# LED_CUBE_595.net
KiCad netlist of a schematic drawn in EAGLE
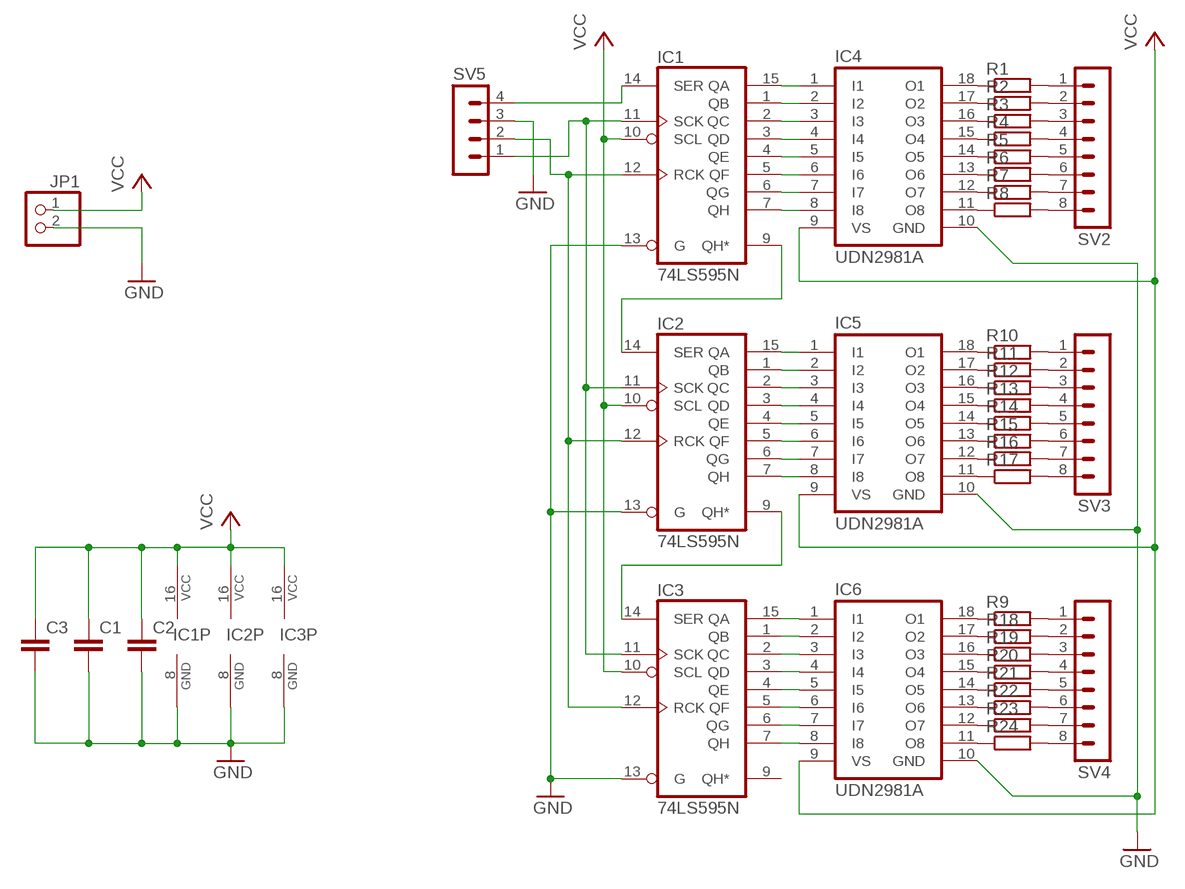
[diagram p0: schematic, sheet 1]

(export (version "E")
  (design (tool "Eeschema 10.0.6"))
  (components
    (comp (ref "C1")
      (value "C-EU025-025X050")
      (footprint "eagle-import:C025-025X050")
      (libsource (lib "eagle-import") (part "C-EU025-025X050"))
    )
    (comp (ref "C2")
      (value "C-EU025-025X050")
      (footprint "eagle-import:C025-025X050")
      (libsource (lib "eagle-import") (part "C-EU025-025X050"))
    )
    (comp (ref "C3")
      (value "C-EU025-025X050")
      (footprint "eagle-import:C025-025X050")
      (libsource (lib "eagle-import") (part "C-EU025-025X050"))
    )
    (comp (ref "IC1")
      (value "74LS595N")
      (footprint "eagle-import:DIL16")
      (libsource (lib "eagle-import") (part "74595NLS"))
    )
    (comp (ref "IC2")
      (value "74LS595N")
      (footprint "eagle-import:DIL16")
      (libsource (lib "eagle-import") (part "74595NLS"))
    )
    (comp (ref "IC3")
      (value "74LS595N")
      (footprint "eagle-import:DIL16")
      (libsource (lib "eagle-import") (part "74595NLS"))
    )
    (comp (ref "IC4")
      (value "UDN2981A")
      (footprint "eagle-import:DIL18")
      (libsource (lib "eagle-import") (part "UDN298A1"))
    )
    (comp (ref "IC5")
      (value "UDN2981A")
      (footprint "eagle-import:DIL18")
      (libsource (lib "eagle-import") (part "UDN298A1"))
    )
    (comp (ref "IC6")
      (value "UDN2981A")
      (footprint "eagle-import:DIL18")
      (libsource (lib "eagle-import") (part "UDN298A1"))
    )
    (comp (ref "JP1")
      (value "PINHD-1X2")
      (footprint "eagle-import:1X02")
      (libsource (lib "eagle-import") (part "PINHD-1X2"))
    )
    (comp (ref "R1")
      (value "R-EU_0204/2V")
      (footprint "eagle-import:0204V")
      (libsource (lib "eagle-import") (part "R-EU_0204/2V"))
    )
    (comp (ref "R2")
      (value "R-EU_0204/2V")
      (footprint "eagle-import:0204V")
      (libsource (lib "eagle-import") (part "R-EU_0204/2V"))
    )
    (comp (ref "R3")
      (value "R-EU_0204/2V")
      (footprint "eagle-import:0204V")
      (libsource (lib "eagle-import") (part "R-EU_0204/2V"))
    )
    (comp (ref "R4")
      (value "R-EU_0204/2V")
      (footprint "eagle-import:0204V")
      (libsource (lib "eagle-import") (part "R-EU_0204/2V"))
    )
    (comp (ref "R5")
      (value "R-EU_0204/2V")
      (footprint "eagle-import:0204V")
      (libsource (lib "eagle-import") (part "R-EU_0204/2V"))
    )
    (comp (ref "R6")
      (value "R-EU_0204/2V")
      (footprint "eagle-import:0204V")
      (libsource (lib "eagle-import") (part "R-EU_0204/2V"))
    )
    (comp (ref "R7")
      (value "R-EU_0204/2V")
      (footprint "eagle-import:0204V")
      (libsource (lib "eagle-import") (part "R-EU_0204/2V"))
    )
    (comp (ref "R8")
      (value "R-EU_0204/2V")
      (footprint "eagle-import:0204V")
      (libsource (lib "eagle-import") (part "R-EU_0204/2V"))
    )
    (comp (ref "R9")
      (value "R-EU_0204/2V")
      (footprint "eagle-import:0204V")
      (libsource (lib "eagle-import") (part "R-EU_0204/2V"))
    )
    (comp (ref "R10")
      (value "R-EU_0204/2V")
      (footprint "eagle-import:0204V")
      (libsource (lib "eagle-import") (part "R-EU_0204/2V"))
    )
    (comp (ref "R11")
      (value "R-EU_0204/2V")
      (footprint "eagle-import:0204V")
      (libsource (lib "eagle-import") (part "R-EU_0204/2V"))
    )
    (comp (ref "R12")
      (value "R-EU_0204/2V")
      (footprint "eagle-import:0204V")
      (libsource (lib "eagle-import") (part "R-EU_0204/2V"))
    )
    (comp (ref "R13")
      (value "R-EU_0204/2V")
      (footprint "eagle-import:0204V")
      (libsource (lib "eagle-import") (part "R-EU_0204/2V"))
    )
    (comp (ref "R14")
      (value "R-EU_0204/2V")
      (footprint "eagle-import:0204V")
      (libsource (lib "eagle-import") (part "R-EU_0204/2V"))
    )
    (comp (ref "R15")
      (value "R-EU_0204/2V")
      (footprint "eagle-import:0204V")
      (libsource (lib "eagle-import") (part "R-EU_0204/2V"))
    )
    (comp (ref "R16")
      (value "R-EU_0204/2V")
      (footprint "eagle-import:0204V")
      (libsource (lib "eagle-import") (part "R-EU_0204/2V"))
    )
    (comp (ref "R17")
      (value "R-EU_0204/2V")
      (footprint "eagle-import:0204V")
      (libsource (lib "eagle-import") (part "R-EU_0204/2V"))
    )
    (comp (ref "R18")
      (value "R-EU_0204/2V")
      (footprint "eagle-import:0204V")
      (libsource (lib "eagle-import") (part "R-EU_0204/2V"))
    )
    (comp (ref "R19")
      (value "R-EU_0204/2V")
      (footprint "eagle-import:0204V")
      (libsource (lib "eagle-import") (part "R-EU_0204/2V"))
    )
    (comp (ref "R20")
      (value "R-EU_0204/2V")
      (footprint "eagle-import:0204V")
      (libsource (lib "eagle-import") (part "R-EU_0204/2V"))
    )
    (comp (ref "R21")
      (value "R-EU_0204/2V")
      (footprint "eagle-import:0204V")
      (libsource (lib "eagle-import") (part "R-EU_0204/2V"))
    )
    (comp (ref "R22")
      (value "R-EU_0204/2V")
      (footprint "eagle-import:0204V")
      (libsource (lib "eagle-import") (part "R-EU_0204/2V"))
    )
    (comp (ref "R23")
      (value "R-EU_0204/2V")
      (footprint "eagle-import:0204V")
      (libsource (lib "eagle-import") (part "R-EU_0204/2V"))
    )
    (comp (ref "R24")
      (value "R-EU_0204/2V")
      (footprint "eagle-import:0204V")
      (libsource (lib "eagle-import") (part "R-EU_0204/2V"))
    )
    (comp (ref "SV2")
      (value "MA08-1")
      (footprint "eagle-import:MA08-1")
      (libsource (lib "eagle-import") (part "MA08-1"))
    )
    (comp (ref "SV3")
      (value "MA08-1")
      (footprint "eagle-import:MA08-1")
      (libsource (lib "eagle-import") (part "MA08-1"))
    )
    (comp (ref "SV4")
      (value "MA08-1")
      (footprint "eagle-import:MA08-1")
      (libsource (lib "eagle-import") (part "MA08-1"))
    )
    (comp (ref "SV5")
      (value "MA04-1")
      (footprint "eagle-import:MA04-1")
      (libsource (lib "eagle-import") (part "MA04-1"))
    )
  )
  (nets
    (net (code "1") (name "GND") (class "Default")
      (node (ref "C1") (pin "2") (pinfunction "2_2") (pintype "passive"))
      (node (ref "C2") (pin "2") (pinfunction "2_2") (pintype "passive"))
      (node (ref "C3") (pin "2") (pinfunction "2_2") (pintype "passive"))
      (node (ref "IC1") (pin "13") (pinfunction "G_13") (pintype "input"))
      (node (ref "IC1") (pin "8") (pinfunction "GND_8") (pintype "power_in"))
      (node (ref "IC2") (pin "13") (pinfunction "G_13") (pintype "input"))
      (node (ref "IC2") (pin "8") (pinfunction "GND_8") (pintype "power_in"))
      (node (ref "IC3") (pin "13") (pinfunction "G_13") (pintype "input"))
      (node (ref "IC3") (pin "8") (pinfunction "GND_8") (pintype "power_in"))
      (node (ref "IC4") (pin "10") (pinfunction "GND_10") (pintype "power_in"))
      (node (ref "IC5") (pin "10") (pinfunction "GND_10") (pintype "power_in"))
      (node (ref "IC6") (pin "10") (pinfunction "GND_10") (pintype "power_in"))
      (node (ref "JP1") (pin "2") (pinfunction "2_2") (pintype "passive"))
      (node (ref "SV5") (pin "3") (pinfunction "3_3") (pintype "passive"))
    )
    (net (code "2") (name "Net-(IC1A-QA)") (class "Default")
      (node (ref "IC1") (pin "15") (pinfunction "QA_15") (pintype "tri_state"))
      (node (ref "IC4") (pin "1") (pinfunction "I1_1") (pintype "input"))
    )
    (net (code "3") (name "Net-(IC1A-QB)") (class "Default")
      (node (ref "IC1") (pin "1") (pinfunction "QB_1") (pintype "tri_state"))
      (node (ref "IC4") (pin "2") (pinfunction "I2_2") (pintype "input"))
    )
    (net (code "4") (name "Net-(IC1A-QC)") (class "Default")
      (node (ref "IC1") (pin "2") (pinfunction "QC_2") (pintype "tri_state"))
      (node (ref "IC4") (pin "3") (pinfunction "I3_3") (pintype "input"))
    )
    (net (code "5") (name "Net-(IC1A-QD)") (class "Default")
      (node (ref "IC1") (pin "3") (pinfunction "QD_3") (pintype "tri_state"))
      (node (ref "IC4") (pin "4") (pinfunction "I4_4") (pintype "input"))
    )
    (net (code "6") (name "Net-(IC1A-QE)") (class "Default")
      (node (ref "IC1") (pin "4") (pinfunction "QE_4") (pintype "tri_state"))
      (node (ref "IC4") (pin "5") (pinfunction "I5_5") (pintype "input"))
    )
    (net (code "7") (name "Net-(IC1A-QF)") (class "Default")
      (node (ref "IC1") (pin "5") (pinfunction "QF_5") (pintype "tri_state"))
      (node (ref "IC4") (pin "6") (pinfunction "I6_6") (pintype "input"))
    )
    (net (code "8") (name "Net-(IC1A-QG)") (class "Default")
      (node (ref "IC1") (pin "6") (pinfunction "QG_6") (pintype "tri_state"))
      (node (ref "IC4") (pin "7") (pinfunction "I7_7") (pintype "input"))
    )
    (net (code "9") (name "Net-(IC1A-QH)") (class "Default")
      (node (ref "IC1") (pin "7") (pinfunction "QH_7") (pintype "tri_state"))
      (node (ref "IC4") (pin "8") (pinfunction "I8_8") (pintype "input"))
    )
    (net (code "10") (name "Net-(IC1A-QH*)") (class "Default")
      (node (ref "IC1") (pin "9") (pinfunction "QH*_9") (pintype "tri_state"))
      (node (ref "IC2") (pin "14") (pinfunction "SER_14") (pintype "input"))
    )
    (net (code "11") (name "Net-(IC1A-RCK)") (class "Default")
      (node (ref "IC1") (pin "12") (pinfunction "RCK_12") (pintype "input"))
      (node (ref "IC2") (pin "12") (pinfunction "RCK_12") (pintype "input"))
      (node (ref "IC3") (pin "12") (pinfunction "RCK_12") (pintype "input"))
      (node (ref "SV5") (pin "2") (pinfunction "2_2") (pintype "passive"))
    )
    (net (code "12") (name "Net-(IC1A-SCK)") (class "Default")
      (node (ref "IC1") (pin "11") (pinfunction "SCK_11") (pintype "input"))
      (node (ref "IC2") (pin "11") (pinfunction "SCK_11") (pintype "input"))
      (node (ref "IC3") (pin "11") (pinfunction "SCK_11") (pintype "input"))
      (node (ref "SV5") (pin "1") (pinfunction "1_1") (pintype "passive"))
    )
    (net (code "13") (name "Net-(IC1A-SER)") (class "Default")
      (node (ref "IC1") (pin "14") (pinfunction "SER_14") (pintype "input"))
      (node (ref "SV5") (pin "4") (pinfunction "4_4") (pintype "passive"))
    )
    (net (code "14") (name "Net-(IC2A-QA)") (class "Default")
      (node (ref "IC2") (pin "15") (pinfunction "QA_15") (pintype "tri_state"))
      (node (ref "IC5") (pin "1") (pinfunction "I1_1") (pintype "input"))
    )
    (net (code "15") (name "Net-(IC2A-QB)") (class "Default")
      (node (ref "IC2") (pin "1") (pinfunction "QB_1") (pintype "tri_state"))
      (node (ref "IC5") (pin "2") (pinfunction "I2_2") (pintype "input"))
    )
    (net (code "16") (name "Net-(IC2A-QC)") (class "Default")
      (node (ref "IC2") (pin "2") (pinfunction "QC_2") (pintype "tri_state"))
      (node (ref "IC5") (pin "3") (pinfunction "I3_3") (pintype "input"))
    )
    (net (code "17") (name "Net-(IC2A-QD)") (class "Default")
      (node (ref "IC2") (pin "3") (pinfunction "QD_3") (pintype "tri_state"))
      (node (ref "IC5") (pin "4") (pinfunction "I4_4") (pintype "input"))
    )
    (net (code "18") (name "Net-(IC2A-QE)") (class "Default")
      (node (ref "IC2") (pin "4") (pinfunction "QE_4") (pintype "tri_state"))
      (node (ref "IC5") (pin "5") (pinfunction "I5_5") (pintype "input"))
    )
    (net (code "19") (name "Net-(IC2A-QF)") (class "Default")
      (node (ref "IC2") (pin "5") (pinfunction "QF_5") (pintype "tri_state"))
      (node (ref "IC5") (pin "6") (pinfunction "I6_6") (pintype "input"))
    )
    (net (code "20") (name "Net-(IC2A-QG)") (class "Default")
      (node (ref "IC2") (pin "6") (pinfunction "QG_6") (pintype "tri_state"))
      (node (ref "IC5") (pin "7") (pinfunction "I7_7") (pintype "input"))
    )
    (net (code "21") (name "Net-(IC2A-QH)") (class "Default")
      (node (ref "IC2") (pin "7") (pinfunction "QH_7") (pintype "tri_state"))
      (node (ref "IC5") (pin "8") (pinfunction "I8_8") (pintype "input"))
    )
    (net (code "22") (name "Net-(IC2A-QH*)") (class "Default")
      (node (ref "IC2") (pin "9") (pinfunction "QH*_9") (pintype "tri_state"))
      (node (ref "IC3") (pin "14") (pinfunction "SER_14") (pintype "input"))
    )
    (net (code "23") (name "Net-(IC3A-QA)") (class "Default")
      (node (ref "IC3") (pin "15") (pinfunction "QA_15") (pintype "tri_state"))
      (node (ref "IC6") (pin "1") (pinfunction "I1_1") (pintype "input"))
    )
    (net (code "24") (name "Net-(IC3A-QB)") (class "Default")
      (node (ref "IC3") (pin "1") (pinfunction "QB_1") (pintype "tri_state"))
      (node (ref "IC6") (pin "2") (pinfunction "I2_2") (pintype "input"))
    )
    (net (code "25") (name "Net-(IC3A-QC)") (class "Default")
      (node (ref "IC3") (pin "2") (pinfunction "QC_2") (pintype "tri_state"))
      (node (ref "IC6") (pin "3") (pinfunction "I3_3") (pintype "input"))
    )
    (net (code "26") (name "Net-(IC3A-QD)") (class "Default")
      (node (ref "IC3") (pin "3") (pinfunction "QD_3") (pintype "tri_state"))
      (node (ref "IC6") (pin "4") (pinfunction "I4_4") (pintype "input"))
    )
    (net (code "27") (name "Net-(IC3A-QE)") (class "Default")
      (node (ref "IC3") (pin "4") (pinfunction "QE_4") (pintype "tri_state"))
      (node (ref "IC6") (pin "5") (pinfunction "I5_5") (pintype "input"))
    )
    (net (code "28") (name "Net-(IC3A-QF)") (class "Default")
      (node (ref "IC3") (pin "5") (pinfunction "QF_5") (pintype "tri_state"))
      (node (ref "IC6") (pin "6") (pinfunction "I6_6") (pintype "input"))
    )
    (net (code "29") (name "Net-(IC3A-QG)") (class "Default")
      (node (ref "IC3") (pin "6") (pinfunction "QG_6") (pintype "tri_state"))
      (node (ref "IC6") (pin "7") (pinfunction "I7_7") (pintype "input"))
    )
    (net (code "30") (name "Net-(IC3A-QH)") (class "Default")
      (node (ref "IC3") (pin "7") (pinfunction "QH_7") (pintype "tri_state"))
      (node (ref "IC6") (pin "8") (pinfunction "I8_8") (pintype "input"))
    )
    (net (code "31") (name "Net-(IC4-O1)") (class "Default")
      (node (ref "IC4") (pin "18") (pinfunction "O1_18") (pintype "open_collector"))
      (node (ref "R1") (pin "1") (pinfunction "1_1") (pintype "passive"))
    )
    (net (code "32") (name "Net-(IC4-O2)") (class "Default")
      (node (ref "IC4") (pin "17") (pinfunction "O2_17") (pintype "open_collector"))
      (node (ref "R2") (pin "1") (pinfunction "1_1") (pintype "passive"))
    )
    (net (code "33") (name "Net-(IC4-O3)") (class "Default")
      (node (ref "IC4") (pin "16") (pinfunction "O3_16") (pintype "open_collector"))
      (node (ref "R3") (pin "1") (pinfunction "1_1") (pintype "passive"))
    )
    (net (code "34") (name "Net-(IC4-O4)") (class "Default")
      (node (ref "IC4") (pin "15") (pinfunction "O4_15") (pintype "open_collector"))
      (node (ref "R4") (pin "1") (pinfunction "1_1") (pintype "passive"))
    )
    (net (code "35") (name "Net-(IC4-O5)") (class "Default")
      (node (ref "IC4") (pin "14") (pinfunction "O5_14") (pintype "open_collector"))
      (node (ref "R5") (pin "1") (pinfunction "1_1") (pintype "passive"))
    )
    (net (code "36") (name "Net-(IC4-O6)") (class "Default")
      (node (ref "IC4") (pin "13") (pinfunction "O6_13") (pintype "open_collector"))
      (node (ref "R6") (pin "1") (pinfunction "1_1") (pintype "passive"))
    )
    (net (code "37") (name "Net-(IC4-O7)") (class "Default")
      (node (ref "IC4") (pin "12") (pinfunction "O7_12") (pintype "open_collector"))
      (node (ref "R7") (pin "1") (pinfunction "1_1") (pintype "passive"))
    )
    (net (code "38") (name "Net-(IC4-O8)") (class "Default")
      (node (ref "IC4") (pin "11") (pinfunction "O8_11") (pintype "open_collector"))
      (node (ref "R8") (pin "1") (pinfunction "1_1") (pintype "passive"))
    )
    (net (code "39") (name "Net-(IC5-O1)") (class "Default")
      (node (ref "IC5") (pin "18") (pinfunction "O1_18") (pintype "open_collector"))
      (node (ref "R10") (pin "1") (pinfunction "1_1") (pintype "passive"))
    )
    (net (code "40") (name "Net-(IC5-O2)") (class "Default")
      (node (ref "IC5") (pin "17") (pinfunction "O2_17") (pintype "open_collector"))
      (node (ref "R11") (pin "1") (pinfunction "1_1") (pintype "passive"))
    )
    (net (code "41") (name "Net-(IC5-O3)") (class "Default")
      (node (ref "IC5") (pin "16") (pinfunction "O3_16") (pintype "open_collector"))
      (node (ref "R12") (pin "1") (pinfunction "1_1") (pintype "passive"))
    )
    (net (code "42") (name "Net-(IC5-O4)") (class "Default")
      (node (ref "IC5") (pin "15") (pinfunction "O4_15") (pintype "open_collector"))
      (node (ref "R13") (pin "1") (pinfunction "1_1") (pintype "passive"))
    )
    (net (code "43") (name "Net-(IC5-O5)") (class "Default")
      (node (ref "IC5") (pin "14") (pinfunction "O5_14") (pintype "open_collector"))
      (node (ref "R14") (pin "1") (pinfunction "1_1") (pintype "passive"))
    )
    (net (code "44") (name "Net-(IC5-O6)") (class "Default")
      (node (ref "IC5") (pin "13") (pinfunction "O6_13") (pintype "open_collector"))
      (node (ref "R15") (pin "1") (pinfunction "1_1") (pintype "passive"))
    )
    (net (code "45") (name "Net-(IC5-O7)") (class "Default")
      (node (ref "IC5") (pin "12") (pinfunction "O7_12") (pintype "open_collector"))
      (node (ref "R16") (pin "1") (pinfunction "1_1") (pintype "passive"))
    )
    (net (code "46") (name "Net-(IC5-O8)") (class "Default")
      (node (ref "IC5") (pin "11") (pinfunction "O8_11") (pintype "open_collector"))
      (node (ref "R17") (pin "1") (pinfunction "1_1") (pintype "passive"))
    )
    (net (code "47") (name "Net-(IC6-O1)") (class "Default")
      (node (ref "IC6") (pin "18") (pinfunction "O1_18") (pintype "open_collector"))
      (node (ref "R9") (pin "1") (pinfunction "1_1") (pintype "passive"))
    )
    (net (code "48") (name "Net-(IC6-O2)") (class "Default")
      (node (ref "IC6") (pin "17") (pinfunction "O2_17") (pintype "open_collector"))
      (node (ref "R18") (pin "1") (pinfunction "1_1") (pintype "passive"))
    )
    (net (code "49") (name "Net-(IC6-O3)") (class "Default")
      (node (ref "IC6") (pin "16") (pinfunction "O3_16") (pintype "open_collector"))
      (node (ref "R19") (pin "1") (pinfunction "1_1") (pintype "passive"))
    )
    (net (code "50") (name "Net-(IC6-O4)") (class "Default")
      (node (ref "IC6") (pin "15") (pinfunction "O4_15") (pintype "open_collector"))
      (node (ref "R20") (pin "1") (pinfunction "1_1") (pintype "passive"))
    )
    (net (code "51") (name "Net-(IC6-O5)") (class "Default")
      (node (ref "IC6") (pin "14") (pinfunction "O5_14") (pintype "open_collector"))
      (node (ref "R21") (pin "1") (pinfunction "1_1") (pintype "passive"))
    )
    (net (code "52") (name "Net-(IC6-O6)") (class "Default")
      (node (ref "IC6") (pin "13") (pinfunction "O6_13") (pintype "open_collector"))
      (node (ref "R22") (pin "1") (pinfunction "1_1") (pintype "passive"))
    )
    (net (code "53") (name "Net-(IC6-O7)") (class "Default")
      (node (ref "IC6") (pin "12") (pinfunction "O7_12") (pintype "open_collector"))
      (node (ref "R23") (pin "1") (pinfunction "1_1") (pintype "passive"))
    )
    (net (code "54") (name "Net-(IC6-O8)") (class "Default")
      (node (ref "IC6") (pin "11") (pinfunction "O8_11") (pintype "open_collector"))
      (node (ref "R24") (pin "1") (pinfunction "1_1") (pintype "passive"))
    )
    (net (code "55") (name "Net-(R1-Pad2)") (class "Default")
      (node (ref "R1") (pin "2") (pinfunction "2_2") (pintype "passive"))
      (node (ref "SV2") (pin "1") (pinfunction "1_1") (pintype "passive"))
    )
    (net (code "56") (name "Net-(R2-Pad2)") (class "Default")
      (node (ref "R2") (pin "2") (pinfunction "2_2") (pintype "passive"))
      (node (ref "SV2") (pin "2") (pinfunction "2_2") (pintype "passive"))
    )
    (net (code "57") (name "Net-(R3-Pad2)") (class "Default")
      (node (ref "R3") (pin "2") (pinfunction "2_2") (pintype "passive"))
      (node (ref "SV2") (pin "3") (pinfunction "3_3") (pintype "passive"))
    )
    (net (code "58") (name "Net-(R4-Pad2)") (class "Default")
      (node (ref "R4") (pin "2") (pinfunction "2_2") (pintype "passive"))
      (node (ref "SV2") (pin "4") (pinfunction "4_4") (pintype "passive"))
    )
    (net (code "59") (name "Net-(R5-Pad2)") (class "Default")
      (node (ref "R5") (pin "2") (pinfunction "2_2") (pintype "passive"))
      (node (ref "SV2") (pin "5") (pinfunction "5_5") (pintype "passive"))
    )
    (net (code "60") (name "Net-(R6-Pad2)") (class "Default")
      (node (ref "R6") (pin "2") (pinfunction "2_2") (pintype "passive"))
      (node (ref "SV2") (pin "6") (pinfunction "6_6") (pintype "passive"))
    )
    (net (code "61") (name "Net-(R7-Pad2)") (class "Default")
      (node (ref "R7") (pin "2") (pinfunction "2_2") (pintype "passive"))
      (node (ref "SV2") (pin "7") (pinfunction "7_7") (pintype "passive"))
    )
    (net (code "62") (name "Net-(R8-Pad2)") (class "Default")
      (node (ref "R8") (pin "2") (pinfunction "2_2") (pintype "passive"))
      (node (ref "SV2") (pin "8") (pinfunction "8_8") (pintype "passive"))
    )
    (net (code "63") (name "Net-(R9-Pad2)") (class "Default")
      (node (ref "R9") (pin "2") (pinfunction "2_2") (pintype "passive"))
      (node (ref "SV4") (pin "1") (pinfunction "1_1") (pintype "passive"))
    )
    (net (code "64") (name "Net-(R10-Pad2)") (class "Default")
      (node (ref "R10") (pin "2") (pinfunction "2_2") (pintype "passive"))
      (node (ref "SV3") (pin "1") (pinfunction "1_1") (pintype "passive"))
    )
    (net (code "65") (name "Net-(R11-Pad2)") (class "Default")
      (node (ref "R11") (pin "2") (pinfunction "2_2") (pintype "passive"))
      (node (ref "SV3") (pin "2") (pinfunction "2_2") (pintype "passive"))
    )
    (net (code "66") (name "Net-(R12-Pad2)") (class "Default")
      (node (ref "R12") (pin "2") (pinfunction "2_2") (pintype "passive"))
      (node (ref "SV3") (pin "3") (pinfunction "3_3") (pintype "passive"))
    )
    (net (code "67") (name "Net-(R13-Pad2)") (class "Default")
      (node (ref "R13") (pin "2") (pinfunction "2_2") (pintype "passive"))
      (node (ref "SV3") (pin "4") (pinfunction "4_4") (pintype "passive"))
    )
    (net (code "68") (name "Net-(R14-Pad2)") (class "Default")
      (node (ref "R14") (pin "2") (pinfunction "2_2") (pintype "passive"))
      (node (ref "SV3") (pin "5") (pinfunction "5_5") (pintype "passive"))
    )
    (net (code "69") (name "Net-(R15-Pad2)") (class "Default")
      (node (ref "R15") (pin "2") (pinfunction "2_2") (pintype "passive"))
      (node (ref "SV3") (pin "6") (pinfunction "6_6") (pintype "passive"))
    )
    (net (code "70") (name "Net-(R16-Pad2)") (class "Default")
      (node (ref "R16") (pin "2") (pinfunction "2_2") (pintype "passive"))
      (node (ref "SV3") (pin "7") (pinfunction "7_7") (pintype "passive"))
    )
    (net (code "71") (name "Net-(R17-Pad2)") (class "Default")
      (node (ref "R17") (pin "2") (pinfunction "2_2") (pintype "passive"))
      (node (ref "SV3") (pin "8") (pinfunction "8_8") (pintype "passive"))
    )
    (net (code "72") (name "Net-(R18-Pad2)") (class "Default")
      (node (ref "R18") (pin "2") (pinfunction "2_2") (pintype "passive"))
      (node (ref "SV4") (pin "2") (pinfunction "2_2") (pintype "passive"))
    )
    (net (code "73") (name "Net-(R19-Pad2)") (class "Default")
      (node (ref "R19") (pin "2") (pinfunction "2_2") (pintype "passive"))
      (node (ref "SV4") (pin "3") (pinfunction "3_3") (pintype "passive"))
    )
    (net (code "74") (name "Net-(R20-Pad2)") (class "Default")
      (node (ref "R20") (pin "2") (pinfunction "2_2") (pintype "passive"))
      (node (ref "SV4") (pin "4") (pinfunction "4_4") (pintype "passive"))
    )
    (net (code "75") (name "Net-(R21-Pad2)") (class "Default")
      (node (ref "R21") (pin "2") (pinfunction "2_2") (pintype "passive"))
      (node (ref "SV4") (pin "5") (pinfunction "5_5") (pintype "passive"))
    )
    (net (code "76") (name "Net-(R22-Pad2)") (class "Default")
      (node (ref "R22") (pin "2") (pinfunction "2_2") (pintype "passive"))
      (node (ref "SV4") (pin "6") (pinfunction "6_6") (pintype "passive"))
    )
    (net (code "77") (name "Net-(R23-Pad2)") (class "Default")
      (node (ref "R23") (pin "2") (pinfunction "2_2") (pintype "passive"))
      (node (ref "SV4") (pin "7") (pinfunction "7_7") (pintype "passive"))
    )
    (net (code "78") (name "Net-(R24-Pad2)") (class "Default")
      (node (ref "R24") (pin "2") (pinfunction "2_2") (pintype "passive"))
      (node (ref "SV4") (pin "8") (pinfunction "8_8") (pintype "passive"))
    )
    (net (code "79") (name "VCC") (class "Default")
      (node (ref "C1") (pin "1") (pinfunction "1_1") (pintype "passive"))
      (node (ref "C2") (pin "1") (pinfunction "1_1") (pintype "passive"))
      (node (ref "C3") (pin "1") (pinfunction "1_1") (pintype "passive"))
      (node (ref "IC1") (pin "10") (pinfunction "SCL_10") (pintype "input"))
      (node (ref "IC1") (pin "16") (pinfunction "VCC_16") (pintype "power_in"))
      (node (ref "IC2") (pin "10") (pinfunction "SCL_10") (pintype "input"))
      (node (ref "IC2") (pin "16") (pinfunction "VCC_16") (pintype "power_in"))
      (node (ref "IC3") (pin "10") (pinfunction "SCL_10") (pintype "input"))
      (node (ref "IC3") (pin "16") (pinfunction "VCC_16") (pintype "power_in"))
      (node (ref "IC4") (pin "9") (pinfunction "VS_9") (pintype "passive"))
      (node (ref "IC5") (pin "9") (pinfunction "VS_9") (pintype "passive"))
      (node (ref "IC6") (pin "9") (pinfunction "VS_9") (pintype "passive"))
      (node (ref "JP1") (pin "1") (pinfunction "1_1") (pintype "passive"))
    )
    (net (code "80") (name "unconnected-(IC3A-QH*-Pad9)") (class "Default")
      (node (ref "IC3") (pin "9") (pinfunction "QH*_9") (pintype "tri_state"))
    )
  )
)
